# 03_boost_converter.net
KiCad netlist of a schematic drawn in Altium Designer
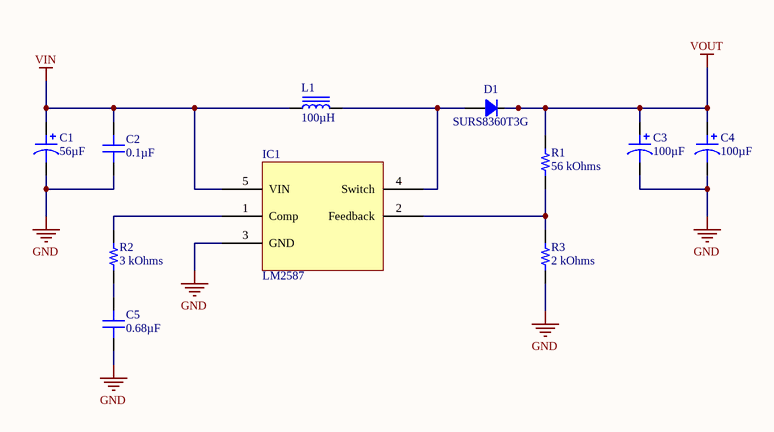
[diagram p0: 03_boost_converter.SchDoc]

(export (version "E")
  (design (tool "Eeschema 10.0.6"))
  (components
    (comp (ref "C1")
      (value "56µF")
      (footprint "CAP ALSMD 6.6MM H7.7MM")
      (description "CAP ALUM 56UF 20% 35V SMD")
      (fields (field (name "PART NUMBER") "UUD1V560MCL1GS") (field (name "MANUFACTURER") "Nichicon"))
      (libsource (lib "Celestial Altium Library - altium_library") (part "Polarised Capacitor"))
    )
    (comp (ref "C2")
      (value "0.1µF")
      (footprint "CAP 0805_2012")
      (description "CAP CER 0.1UF 50V X7R 0805")
      (fields (field (name "PART NUMBER") "VJ0805Y104MXAMR") (field (name "MANUFACTURER") "Vishay Vitramon"))
      (libsource (lib "Celestial Altium Library - altium_library") (part "Capacitor"))
    )
    (comp (ref "C3")
      (value "100µF")
      (footprint "CAP ALSMD 8.3MM H10.5MM")
      (description "CAP ALUM 100UF 20% 50V SMD")
      (fields
        (field (name "PART NUMBER") "EEE-FK1H101P")
        (field (name "MANUFACTURER") "Panasonic Electronic Components")
      )
      (libsource (lib "Celestial Altium Library - altium_library") (part "Polarised Capacitor"))
    )
    (comp (ref "C4")
      (value "100µF")
      (footprint "CAP ALSMD 8.3MM H10.5MM")
      (description "CAP ALUM 100UF 20% 50V SMD")
      (fields
        (field (name "PART NUMBER") "EEE-FK1H101P")
        (field (name "MANUFACTURER") "Panasonic Electronic Components")
      )
      (libsource (lib "Celestial Altium Library - altium_library") (part "Polarised Capacitor"))
    )
    (comp (ref "C5")
      (value "0.68µF")
      (footprint "CAP 0805_2012")
      (description "CAP CER 0.68UF 50V X7R 0805")
      (fields (field (name "PART NUMBER") "C0805X684K5RECAUTO") (field (name "MANUFACTURER") "KEMET"))
      (libsource (lib "Celestial Altium Library - altium_library") (part "Capacitor"))
    )
    (comp (ref "D1")
      (value "SURS8360T3G")
      (footprint "DO214AB SMC")
      (description "DIODE GEN PURP 600V 3A SMC")
      (fields (field (name "MANUFACTURER") "ON Semiconductor"))
      (libsource (lib "Celestial Altium Library - altium_library") (part "Diode"))
    )
    (comp (ref "IC1")
      (value "LM2587")
      (footprint "Kutuphane:D2PAK")
      (description "Boost Converter")
      (libsource (lib "Kutuphane") (part "LM2587"))
    )
    (comp (ref "L1")
      (value "100µH")
      (footprint "Kutuphane:7447070")
      (description "FIXED IND 100UH 2.1A 150MOHM SMD")
      (fields (field (name "PART NUMBER") "SRR1280-101M") (field (name "MANUFACTURER") "Bourns Inc."))
      (libsource (lib "Celestial Altium Library - altium_library") (part "Inductor"))
    )
    (comp (ref "R1")
      (value "56 kOhms")
      (footprint "RES 0805_2012")
      (description "RES SMD 56K OHM 1% 1/8W 0805")
      (fields (field (name "PART NUMBER") "CRCW080556K0FKEA") (field (name "MANUFACTURER") "Vishay Dale"))
      (libsource (lib "Celestial Altium Library - altium_library") (part "Resistor"))
    )
    (comp (ref "R2")
      (value "3 kOhms")
      (footprint "RES 0805_2012")
      (description "RES SMD 3K OHM 1% 1/8W 0805")
      (fields
        (field (name "PART NUMBER") "ERJ-6ENF3001V")
        (field (name "MANUFACTURER") "Panasonic Electronic Components")
      )
      (libsource (lib "Celestial Altium Library - altium_library") (part "Resistor"))
    )
    (comp (ref "R3")
      (value "2 kOhms")
      (footprint "RES 0805_2012")
      (description "RES SMD 2K OHM 1% 1/8W 0805")
      (fields (field (name "PART NUMBER") "RC0805FR-072KP") (field (name "MANUFACTURER") "Yageo"))
      (libsource (lib "Celestial Altium Library - altium_library") (part "Resistor"))
    )
  )
  (nets
    (net (code "1") (name "GND") (class "Default")
      (node (ref "C1") (pin "2") (pinfunction "2_2") (pintype "passive"))
      (node (ref "C2") (pin "1") (pinfunction "1_1") (pintype "passive"))
      (node (ref "C3") (pin "2") (pinfunction "2_2") (pintype "passive"))
      (node (ref "C4") (pin "2") (pinfunction "2_2") (pintype "passive"))
      (node (ref "C5") (pin "1") (pinfunction "1_1") (pintype "passive"))
      (node (ref "IC1") (pin "3") (pinfunction "GND_3") (pintype "passive"))
      (node (ref "R3") (pin "1") (pinfunction "1_1") (pintype "passive"))
    )
    (net (code "2") (name "Net-(C5-Pad2)") (class "Default")
      (node (ref "C5") (pin "2") (pinfunction "2_2") (pintype "passive"))
      (node (ref "R2") (pin "1") (pinfunction "1_1") (pintype "passive"))
    )
    (net (code "3") (name "Net-(IC1-Comp)") (class "Default")
      (node (ref "IC1") (pin "1") (pinfunction "Comp_1") (pintype "passive"))
      (node (ref "R2") (pin "2") (pinfunction "2_2") (pintype "passive"))
    )
    (net (code "4") (name "Net-(IC1-Feedback)") (class "Default")
      (node (ref "IC1") (pin "2") (pinfunction "Feedback_2") (pintype "passive"))
      (node (ref "R1") (pin "1") (pinfunction "1_1") (pintype "passive"))
      (node (ref "R3") (pin "2") (pinfunction "2_2") (pintype "passive"))
    )
    (net (code "5") (name "Net-(IC1-Switch)") (class "Default")
      (node (ref "D1") (pin "1") (pinfunction "1_1") (pintype "passive"))
      (node (ref "IC1") (pin "4") (pinfunction "Switch_4") (pintype "passive"))
      (node (ref "L1") (pin "2") (pinfunction "2_2") (pintype "passive"))
    )
    (net (code "6") (name "VIN") (class "Default")
      (node (ref "C1") (pin "1") (pinfunction "1_1") (pintype "passive"))
      (node (ref "C2") (pin "2") (pinfunction "2_2") (pintype "passive"))
      (node (ref "IC1") (pin "5") (pinfunction "VIN_5") (pintype "passive"))
      (node (ref "L1") (pin "1") (pinfunction "1_1") (pintype "passive"))
    )
    (net (code "7") (name "VOUT") (class "Default")
      (node (ref "C3") (pin "1") (pinfunction "1_1") (pintype "passive"))
      (node (ref "C4") (pin "1") (pinfunction "1_1") (pintype "passive"))
      (node (ref "D1") (pin "2") (pinfunction "2_2") (pintype "passive"))
      (node (ref "R1") (pin "2") (pinfunction "2_2") (pintype "passive"))
    )
  )
)
